# TLV493D-triple.net
KiCad netlist of a schematic drawn in EasyEDA Pro
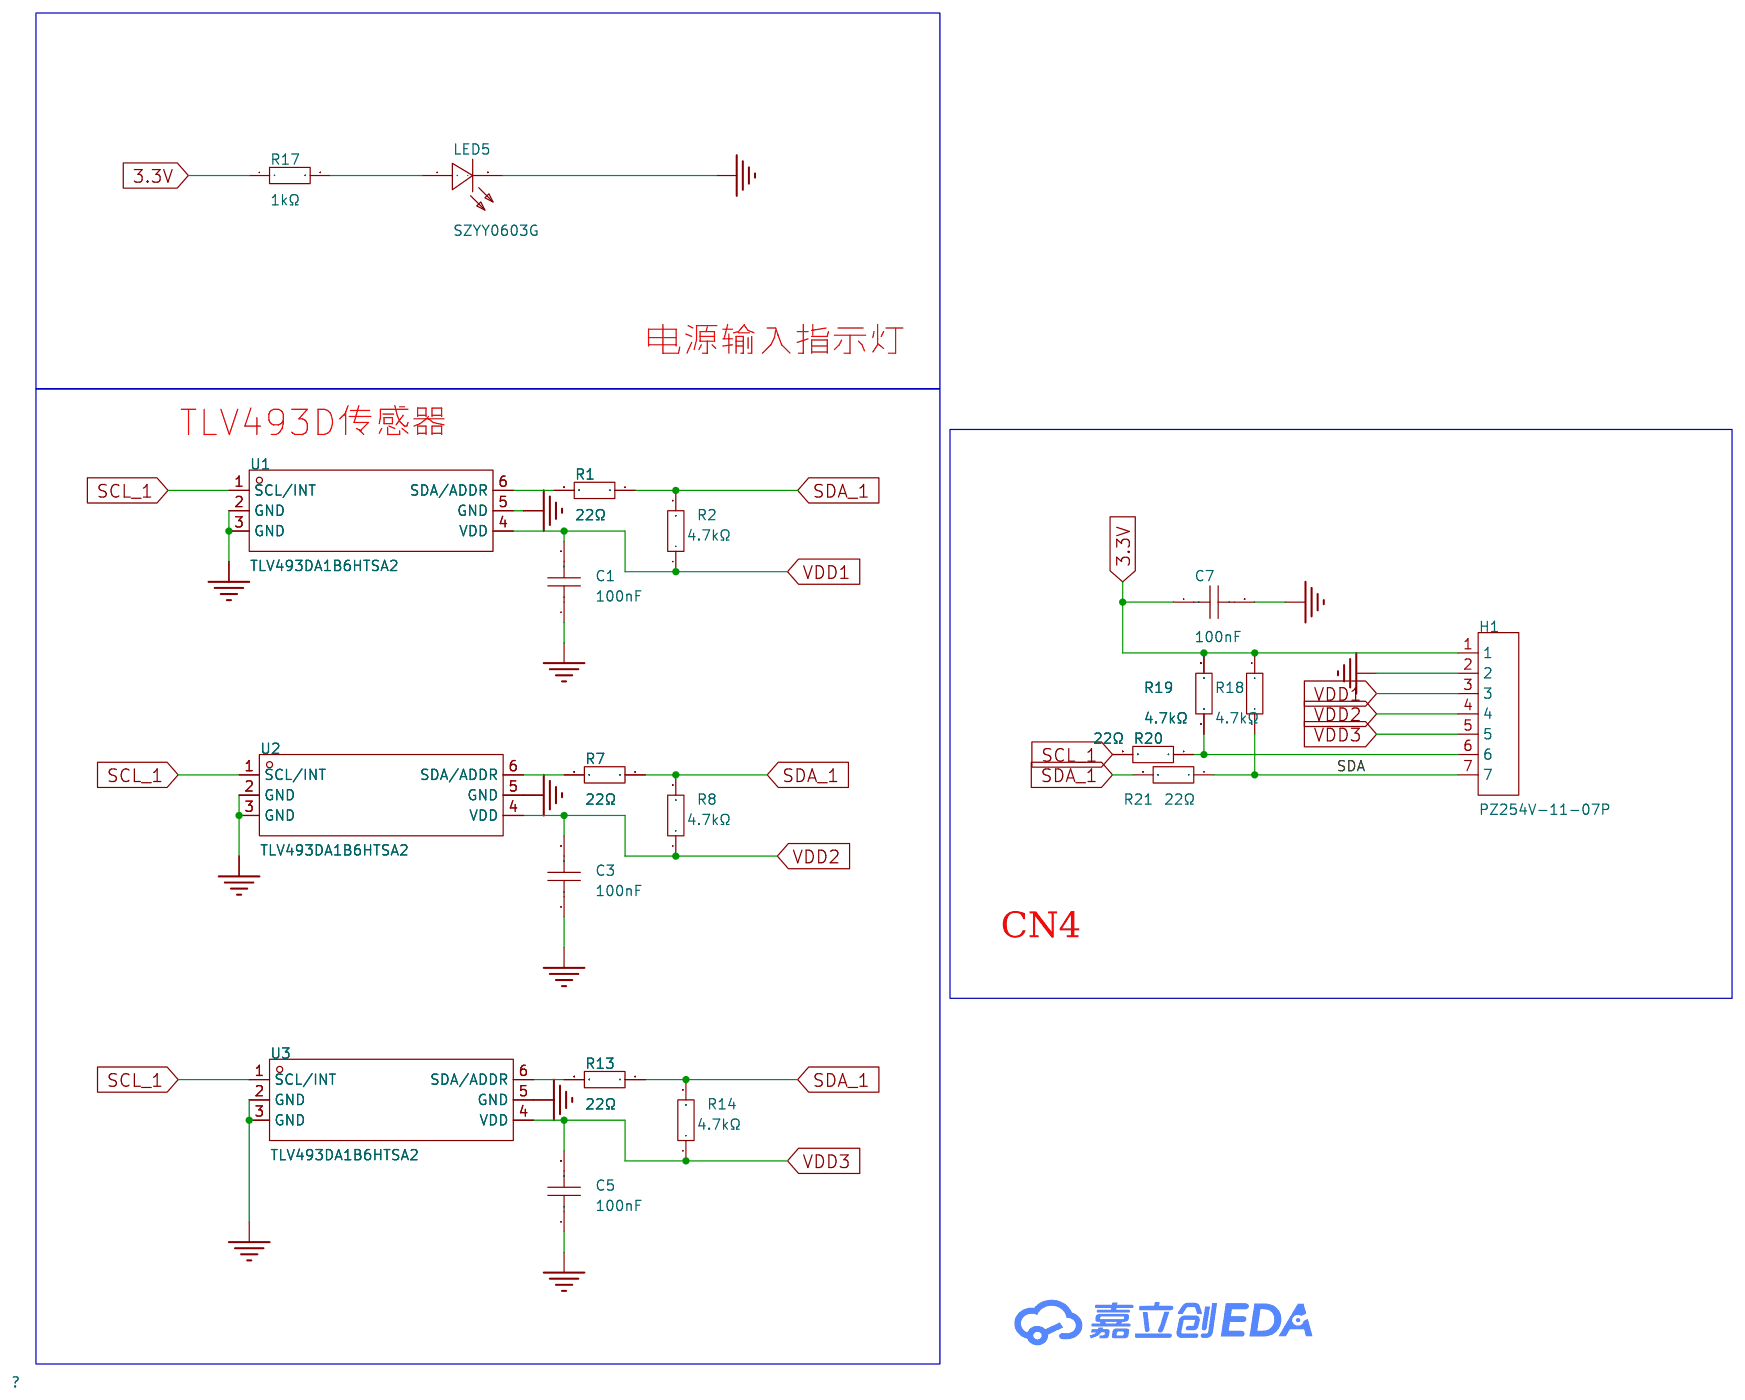
[diagram p0: schematic sheet]

(export (version "E")
  (design (tool "Eeschema 10.0.6"))
  (components
    (comp (ref "C1")
      (value "100nF")
      (footprint "easyedapro:C0603")
      (description "容值:100nF;精度:±10%;额定电压:50V;温度系数:X7R;")
      (fields
        (field (name "Manufacturer Part") "CGA0603X7R104K500JT")
        (field (name "Manufacturer") "HRE(芯声)")
      )
      (libsource (lib "easyedapro") (part "CGA0603X7R104K500JT"))
    )
    (comp (ref "C3")
      (value "100nF")
      (footprint "easyedapro:C0603")
      (description "容值:100nF;精度:±10%;额定电压:50V;温度系数:X7R;")
      (fields
        (field (name "Manufacturer Part") "CGA0603X7R104K500JT")
        (field (name "Manufacturer") "HRE(芯声)")
      )
      (libsource (lib "easyedapro") (part "CGA0603X7R104K500JT"))
    )
    (comp (ref "C5")
      (value "100nF")
      (footprint "easyedapro:C0603")
      (description "容值:100nF;精度:±10%;额定电压:50V;温度系数:X7R;")
      (fields
        (field (name "Manufacturer Part") "CGA0603X7R104K500JT")
        (field (name "Manufacturer") "HRE(芯声)")
      )
      (libsource (lib "easyedapro") (part "CGA0603X7R104K500JT"))
    )
    (comp (ref "C7")
      (value "100nF")
      (footprint "easyedapro:C0603")
      (description "容值:100nF;精度:±10%;额定电压:50V;温度系数:X7R;")
      (fields
        (field (name "Manufacturer Part") "CGA0603X7R104K500JT")
        (field (name "Manufacturer") "HRE(芯声)")
      )
      (libsource (lib "easyedapro") (part "CGA0603X7R104K500JT"))
    )
    (comp (ref "H1")
      (value "PZ254V-11-07P")
      (footprint "easyedapro:HDR-TH_7P-P2.54-V-M")
      (fields (field (name "Manufacturer") "XFCN(兴飞)"))
      (libsource (lib "easyedapro") (part "PZ254V-11-07P"))
    )
    (comp (ref "LED5")
      (value "SZYY0603G")
      (footprint "easyedapro:LED0603-R-RD_GREEN")
      (description "发光颜色:翠绿色;")
      (fields (field (name "Manufacturer") "yongyu(永裕光电)"))
      (libsource (lib "easyedapro") (part "SZYY0603G"))
    )
    (comp (ref "R1")
      (value "22Ω")
      (footprint "easyedapro:R0603")
      (description "电阻类型:厚膜电阻;阻值:22Ω;精度:±1%;功率:100mW;最大工作电压:75V;温度系数:±100ppm/°C;")
      (fields
        (field (name "Manufacturer Part") "0603WAF220JT5E")
        (field (name "Manufacturer") "UNI-ROYAL(厚声)")
      )
      (libsource (lib "easyedapro") (part "0603WAF220JT5E"))
    )
    (comp (ref "R2")
      (value "4.7kΩ")
      (footprint "easyedapro:R0603")
      (description "电阻类型:厚膜电阻;阻值:4.7kΩ;精度:±1%;功率:100mW;最大工作电压:75V;温度系数:±100ppm/°C;")
      (fields
        (field (name "Manufacturer Part") "0603WAF4701T5E")
        (field (name "Manufacturer") "UNI-ROYAL(厚声)")
      )
      (libsource (lib "easyedapro") (part "0603WAF4701T5E"))
    )
    (comp (ref "R7")
      (value "22Ω")
      (footprint "easyedapro:R0603")
      (description "电阻类型:厚膜电阻;阻值:22Ω;精度:±1%;功率:100mW;最大工作电压:75V;温度系数:±100ppm/°C;")
      (fields
        (field (name "Manufacturer Part") "0603WAF220JT5E")
        (field (name "Manufacturer") "UNI-ROYAL(厚声)")
      )
      (libsource (lib "easyedapro") (part "0603WAF220JT5E"))
    )
    (comp (ref "R8")
      (value "4.7kΩ")
      (footprint "easyedapro:R0603")
      (description "电阻类型:厚膜电阻;阻值:4.7kΩ;精度:±1%;功率:100mW;最大工作电压:75V;温度系数:±100ppm/°C;")
      (fields
        (field (name "Manufacturer Part") "0603WAF4701T5E")
        (field (name "Manufacturer") "UNI-ROYAL(厚声)")
      )
      (libsource (lib "easyedapro") (part "0603WAF4701T5E"))
    )
    (comp (ref "R13")
      (value "22Ω")
      (footprint "easyedapro:R0603")
      (description "电阻类型:厚膜电阻;阻值:22Ω;精度:±1%;功率:100mW;最大工作电压:75V;温度系数:±100ppm/°C;")
      (fields
        (field (name "Manufacturer Part") "0603WAF220JT5E")
        (field (name "Manufacturer") "UNI-ROYAL(厚声)")
      )
      (libsource (lib "easyedapro") (part "0603WAF220JT5E"))
    )
    (comp (ref "R14")
      (value "4.7kΩ")
      (footprint "easyedapro:R0603")
      (description "电阻类型:厚膜电阻;阻值:4.7kΩ;精度:±1%;功率:100mW;最大工作电压:75V;温度系数:±100ppm/°C;")
      (fields
        (field (name "Manufacturer Part") "0603WAF4701T5E")
        (field (name "Manufacturer") "UNI-ROYAL(厚声)")
      )
      (libsource (lib "easyedapro") (part "0603WAF4701T5E"))
    )
    (comp (ref "R17")
      (value "1kΩ")
      (footprint "easyedapro:R0603")
      (description "电阻类型:厚膜电阻;阻值:1kΩ;精度:±1%;功率:100mW;最大工作电压:75V;温度系数:±100ppm/°C;")
      (fields
        (field (name "Manufacturer Part") "0603WAF1001T5E")
        (field (name "Manufacturer") "UNI-ROYAL(厚声)")
      )
      (libsource (lib "easyedapro") (part "0603WAF1001T5E"))
    )
    (comp (ref "R18")
      (value "4.7kΩ")
      (footprint "easyedapro:R0603")
      (description "电阻类型:厚膜电阻;阻值:4.7kΩ;精度:±1%;功率:100mW;最大工作电压:75V;温度系数:±100ppm/°C;")
      (fields
        (field (name "Manufacturer Part") "0603WAF4701T5E")
        (field (name "Manufacturer") "UNI-ROYAL(厚声)")
      )
      (libsource (lib "easyedapro") (part "0603WAF4701T5E"))
    )
    (comp (ref "R19")
      (value "4.7kΩ")
      (footprint "easyedapro:R0603")
      (description "电阻类型:厚膜电阻;阻值:4.7kΩ;精度:±1%;功率:100mW;最大工作电压:75V;温度系数:±100ppm/°C;")
      (fields
        (field (name "Manufacturer Part") "0603WAF4701T5E")
        (field (name "Manufacturer") "UNI-ROYAL(厚声)")
      )
      (libsource (lib "easyedapro") (part "0603WAF4701T5E"))
    )
    (comp (ref "R20")
      (value "22Ω")
      (footprint "easyedapro:R0603")
      (description "电阻类型:厚膜电阻;阻值:22Ω;精度:±1%;功率:100mW;最大工作电压:75V;温度系数:±100ppm/°C;")
      (fields
        (field (name "Manufacturer Part") "0603WAF220JT5E")
        (field (name "Manufacturer") "UNI-ROYAL(厚声)")
      )
      (libsource (lib "easyedapro") (part "0603WAF220JT5E"))
    )
    (comp (ref "R21")
      (value "22Ω")
      (footprint "easyedapro:R0603")
      (description "电阻类型:厚膜电阻;阻值:22Ω;精度:±1%;功率:100mW;最大工作电压:75V;温度系数:±100ppm/°C;")
      (fields
        (field (name "Manufacturer Part") "0603WAF220JT5E")
        (field (name "Manufacturer") "UNI-ROYAL(厚声)")
      )
      (libsource (lib "easyedapro") (part "0603WAF220JT5E"))
    )
    (comp (ref "U1")
      (value "TLV493DA1B6HTSA2")
      (footprint "easyedapro:SOP-6_L3.0-W1.5-P0.95-LS2.5-BR")
      (description "3D磁性传感器")
      (fields (field (name "Manufacturer") "Infineon(英飞凌)"))
      (libsource (lib "easyedapro") (part "TLV493DA1B6HTSA2"))
    )
    (comp (ref "U2")
      (value "TLV493DA1B6HTSA2")
      (footprint "easyedapro:SOP-6_L3.0-W1.5-P0.95-LS2.5-BR")
      (description "3D磁性传感器")
      (fields (field (name "Manufacturer") "Infineon(英飞凌)"))
      (libsource (lib "easyedapro") (part "TLV493DA1B6HTSA2"))
    )
    (comp (ref "U3")
      (value "TLV493DA1B6HTSA2")
      (footprint "easyedapro:SOP-6_L3.0-W1.5-P0.95-LS2.5-BR")
      (description "3D磁性传感器")
      (fields (field (name "Manufacturer") "Infineon(英飞凌)"))
      (libsource (lib "easyedapro") (part "TLV493DA1B6HTSA2"))
    )
  )
  (nets
    (net (code "1") (name "/SDA") (class "Default")
      (node (ref "H1") (pin "7") (pinfunction "7_7") (pintype "unspecified"))
      (node (ref "R18") (pin "1") (pinfunction "1_1") (pintype "input"))
      (node (ref "R21") (pin "1") (pinfunction "1_1") (pintype "input"))
    )
    (net (code "2") (name "3.3V") (class "Default")
      (node (ref "C7") (pin "1") (pinfunction "1_1") (pintype "unspecified"))
      (node (ref "H1") (pin "1") (pinfunction "1_1") (pintype "unspecified"))
      (node (ref "R17") (pin "1") (pinfunction "1_1") (pintype "input"))
      (node (ref "R18") (pin "2") (pinfunction "2_2") (pintype "input"))
      (node (ref "R19") (pin "2") (pinfunction "2_2") (pintype "input"))
    )
    (net (code "3") (name "GND") (class "Default")
      (node (ref "C1") (pin "1") (pinfunction "1_1") (pintype "unspecified"))
      (node (ref "C3") (pin "1") (pinfunction "1_1") (pintype "unspecified"))
      (node (ref "C5") (pin "1") (pinfunction "1_1") (pintype "unspecified"))
      (node (ref "C7") (pin "2") (pinfunction "2_2") (pintype "unspecified"))
      (node (ref "H1") (pin "2") (pinfunction "2_2") (pintype "unspecified"))
      (node (ref "LED5") (pin "2") (pinfunction "-_2") (pintype "unspecified"))
      (node (ref "U1") (pin "2") (pinfunction "GND_2") (pintype "unspecified"))
      (node (ref "U1") (pin "3") (pinfunction "GND_3") (pintype "unspecified"))
      (node (ref "U1") (pin "5") (pinfunction "GND_5") (pintype "unspecified"))
      (node (ref "U2") (pin "2") (pinfunction "GND_2") (pintype "unspecified"))
      (node (ref "U2") (pin "3") (pinfunction "GND_3") (pintype "unspecified"))
      (node (ref "U2") (pin "5") (pinfunction "GND_5") (pintype "unspecified"))
      (node (ref "U3") (pin "2") (pinfunction "GND_2") (pintype "unspecified"))
      (node (ref "U3") (pin "3") (pinfunction "GND_3") (pintype "unspecified"))
      (node (ref "U3") (pin "5") (pinfunction "GND_5") (pintype "unspecified"))
    )
    (net (code "4") (name "Net-(H1-Pad6)") (class "Default")
      (node (ref "H1") (pin "6") (pinfunction "6_6") (pintype "unspecified"))
      (node (ref "R19") (pin "1") (pinfunction "1_1") (pintype "input"))
      (node (ref "R20") (pin "1") (pinfunction "1_1") (pintype "input"))
    )
    (net (code "5") (name "Net-(LED5-+)") (class "Default")
      (node (ref "LED5") (pin "1") (pinfunction "+_1") (pintype "unspecified"))
      (node (ref "R17") (pin "2") (pinfunction "2_2") (pintype "input"))
    )
    (net (code "6") (name "Net-(U1-SDA{slash}ADDR)") (class "Default")
      (node (ref "R1") (pin "2") (pinfunction "2_2") (pintype "input"))
      (node (ref "U1") (pin "6") (pinfunction "SDA/ADDR_6") (pintype "unspecified"))
    )
    (net (code "7") (name "Net-(U2-SDA{slash}ADDR)") (class "Default")
      (node (ref "R7") (pin "2") (pinfunction "2_2") (pintype "input"))
      (node (ref "U2") (pin "6") (pinfunction "SDA/ADDR_6") (pintype "unspecified"))
    )
    (net (code "8") (name "Net-(U3-SDA{slash}ADDR)") (class "Default")
      (node (ref "R13") (pin "2") (pinfunction "2_2") (pintype "input"))
      (node (ref "U3") (pin "6") (pinfunction "SDA/ADDR_6") (pintype "unspecified"))
    )
    (net (code "9") (name "SCL_1") (class "Default")
      (node (ref "R20") (pin "2") (pinfunction "2_2") (pintype "input"))
      (node (ref "U1") (pin "1") (pinfunction "SCL/INT_1") (pintype "unspecified"))
      (node (ref "U2") (pin "1") (pinfunction "SCL/INT_1") (pintype "unspecified"))
      (node (ref "U3") (pin "1") (pinfunction "SCL/INT_1") (pintype "unspecified"))
    )
    (net (code "10") (name "SDA_1") (class "Default")
      (node (ref "R1") (pin "1") (pinfunction "1_1") (pintype "input"))
      (node (ref "R13") (pin "1") (pinfunction "1_1") (pintype "input"))
      (node (ref "R14") (pin "2") (pinfunction "2_2") (pintype "input"))
      (node (ref "R2") (pin "2") (pinfunction "2_2") (pintype "input"))
      (node (ref "R21") (pin "2") (pinfunction "2_2") (pintype "input"))
      (node (ref "R7") (pin "1") (pinfunction "1_1") (pintype "input"))
      (node (ref "R8") (pin "2") (pinfunction "2_2") (pintype "input"))
    )
    (net (code "11") (name "VDD1") (class "Default")
      (node (ref "C1") (pin "2") (pinfunction "2_2") (pintype "unspecified"))
      (node (ref "H1") (pin "3") (pinfunction "3_3") (pintype "unspecified"))
      (node (ref "R2") (pin "1") (pinfunction "1_1") (pintype "input"))
      (node (ref "U1") (pin "4") (pinfunction "VDD_4") (pintype "unspecified"))
    )
    (net (code "12") (name "VDD2") (class "Default")
      (node (ref "C3") (pin "2") (pinfunction "2_2") (pintype "unspecified"))
      (node (ref "H1") (pin "4") (pinfunction "4_4") (pintype "unspecified"))
      (node (ref "R8") (pin "1") (pinfunction "1_1") (pintype "input"))
      (node (ref "U2") (pin "4") (pinfunction "VDD_4") (pintype "unspecified"))
    )
    (net (code "13") (name "VDD3") (class "Default")
      (node (ref "C5") (pin "2") (pinfunction "2_2") (pintype "unspecified"))
      (node (ref "H1") (pin "5") (pinfunction "5_5") (pintype "unspecified"))
      (node (ref "R14") (pin "1") (pinfunction "1_1") (pintype "input"))
      (node (ref "U3") (pin "4") (pinfunction "VDD_4") (pintype "unspecified"))
    )
  )
)
